# TransmissorTori.net
KiCad netlist of a schematic drawn in EAGLE
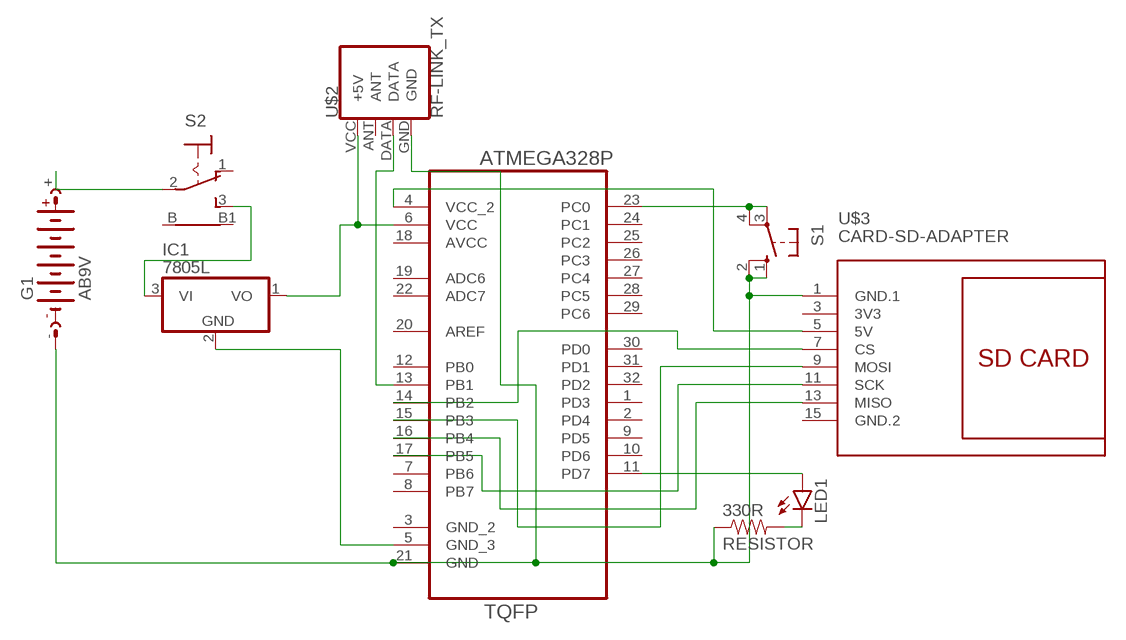
[diagram p0: schematic, sheet 1]

(export (version "E")
  (design (tool "Eeschema 10.0.6"))
  (components
    (comp (ref "330R")
      (value "RESISTOR")
      (footprint "eagle-import:0603RES")
      (libsource (lib "eagle-import") (part "RESISTOR"))
    )
    (comp (ref "G1")
      (value "AB9V")
      (footprint "eagle-import:AB9V")
      (libsource (lib "eagle-import") (part "AB9V"))
    )
    (comp (ref "IC1")
      (value "7805L")
      (footprint "eagle-import:TO92")
      (libsource (lib "eagle-import") (part "78L05"))
    )
    (comp (ref "LED1")
      (value "LED5MM")
      (footprint "eagle-import:LED5MM")
      (libsource (lib "eagle-import") (part "LED5MM"))
    )
    (comp (ref "S1")
      (value "10-XX")
      (footprint "eagle-import:B3F-10XX")
      (fields (field (name "MPN") "B3F-1000"))
      (libsource (lib "eagle-import") (part "10-XX"))
    )
    (comp (ref "S2")
      (value "9070-1W")
      (footprint "eagle-import:9070-1W")
      (libsource (lib "eagle-import") (part "9070-1W"))
    )
    (comp (ref "U$2")
      (value "RF-LINK_TX")
      (footprint "eagle-import:RF-LINK_TX")
      (libsource (lib "eagle-import") (part "RF-LINK_TX"))
    )
    (comp (ref "U$3")
      (value "CARD-SD-ADAPTER")
      (footprint "eagle-import:CARD-SD-ADAPTER")
      (libsource (lib "eagle-import") (part "CARD-SD-ADAPTER"))
    )
    (comp (ref "U1")
      (value "ATMEGA328P-AU")
      (footprint "eagle-import:QFP80P900X900X120-32N")
      (libsource (lib "eagle-import") (part "ATMEGA328P-AU"))
    )
  )
  (nets
    (net (code "1") (name "/3V3") (class "Default")
      (node (ref "U$3") (pin "3") (pinfunction "3V3_3") (pintype "power_in"))
    )
    (net (code "2") (name "/AVCC") (class "Default")
      (node (ref "U1") (pin "18") (pinfunction "AVCC_18") (pintype "power_in"))
    )
    (net (code "3") (name "/GND.2") (class "Default")
      (node (ref "U$3") (pin "15") (pinfunction "GND.2_15") (pintype "power_in"))
    )
    (net (code "4") (name "Net-(IC1-GND)") (class "Default")
      (node (ref "IC1") (pin "2") (pinfunction "GND_2") (pintype "passive"))
      (node (ref "U1") (pin "5") (pinfunction "GND_3_5") (pintype "passive"))
    )
    (net (code "5") (name "Net-(IC1-VI)") (class "Default")
      (node (ref "IC1") (pin "3") (pinfunction "VI_3") (pintype "input"))
      (node (ref "S2") (pin "3") (pinfunction "S_3") (pintype "passive"))
    )
    (net (code "6") (name "Net-(IC1-VO)") (class "Default")
      (node (ref "IC1") (pin "1") (pinfunction "VO_1") (pintype "passive"))
      (node (ref "U$2") (pin "VCC") (pinfunction "+5V_VCC") (pintype "power_in"))
      (node (ref "U1") (pin "6") (pinfunction "VCC_6") (pintype "power_in"))
    )
    (net (code "7") (name "Net-(LED1-C)") (class "Default")
      (node (ref "330R") (pin "2") (pinfunction "2_2") (pintype "passive"))
      (node (ref "LED1") (pin "K") (pinfunction "C_K") (pintype "passive"))
    )
    (net (code "8") (name "Net-(S1-P)") (class "Default")
      (node (ref "S1") (pin "3") (pinfunction "P_3") (pintype "passive"))
      (node (ref "S1") (pin "4") (pinfunction "P1_4") (pintype "passive"))
      (node (ref "U1") (pin "23") (pinfunction "PC0_23") (pintype "bidirectional"))
    )
    (net (code "9") (name "Net-(S1-S)") (class "Default")
      (node (ref "330R") (pin "1") (pinfunction "1_1") (pintype "passive"))
      (node (ref "G1") (pin "-") (pinfunction "-_-") (pintype "passive"))
      (node (ref "S1") (pin "1") (pinfunction "S_1") (pintype "passive"))
      (node (ref "S1") (pin "2") (pinfunction "S1_2") (pintype "passive"))
      (node (ref "U$2") (pin "GND") (pinfunction "GND_GND") (pintype "power_in"))
      (node (ref "U$3") (pin "1") (pinfunction "GND.1_1") (pintype "power_in"))
      (node (ref "U1") (pin "21") (pinfunction "GND_21") (pintype "passive"))
    )
    (net (code "10") (name "Net-(S2-P)") (class "Default")
      (node (ref "G1") (pin "+") (pinfunction "+_+") (pintype "passive"))
      (node (ref "S2") (pin "2") (pinfunction "P_2") (pintype "passive"))
    )
    (net (code "11") (name "Net-(U$3-5V)") (class "Default")
      (node (ref "U$3") (pin "5") (pinfunction "5V_5") (pintype "power_in"))
      (node (ref "U1") (pin "4") (pinfunction "VCC_2_4") (pintype "power_in"))
    )
    (net (code "12") (name "Net-(U$3-CS)") (class "Default")
      (node (ref "U$3") (pin "7") (pinfunction "CS_7") (pintype "bidirectional"))
      (node (ref "U1") (pin "14") (pinfunction "PB2_14") (pintype "bidirectional"))
    )
    (net (code "13") (name "Net-(U$3-MISO)") (class "Default")
      (node (ref "U$3") (pin "13") (pinfunction "MISO_13") (pintype "bidirectional"))
      (node (ref "U1") (pin "16") (pinfunction "PB4_16") (pintype "bidirectional"))
    )
    (net (code "14") (name "Net-(U$3-MOSI)") (class "Default")
      (node (ref "U$3") (pin "9") (pinfunction "MOSI_9") (pintype "bidirectional"))
      (node (ref "U1") (pin "15") (pinfunction "PB3_15") (pintype "bidirectional"))
    )
    (net (code "15") (name "Net-(U$3-SCK)") (class "Default")
      (node (ref "U$3") (pin "11") (pinfunction "SCK_11") (pintype "bidirectional"))
      (node (ref "U1") (pin "17") (pinfunction "PB5_17") (pintype "bidirectional"))
    )
    (net (code "16") (name "Net-(U1-PB1)") (class "Default")
      (node (ref "U$2") (pin "DATA") (pinfunction "DATA_DATA") (pintype "input"))
      (node (ref "U1") (pin "13") (pinfunction "PB1_13") (pintype "bidirectional"))
    )
    (net (code "17") (name "Net-(U1-PD7)") (class "Default")
      (node (ref "LED1") (pin "A") (pinfunction "A_A") (pintype "passive"))
      (node (ref "U1") (pin "11") (pinfunction "PD7_11") (pintype "bidirectional"))
    )
    (net (code "18") (name "unconnected-(S2-O-Pad1)") (class "Default")
      (node (ref "S2") (pin "1") (pinfunction "O_1") (pintype "passive"))
    )
    (net (code "19") (name "unconnected-(S2-PadB)") (class "Default")
      (node (ref "S2") (pin "B") (pinfunction "B_B") (pintype "passive"))
    )
    (net (code "20") (name "unconnected-(S2-PadB1)") (class "Default")
      (node (ref "S2") (pin "B1") (pinfunction "B1_B1") (pintype "passive"))
    )
    (net (code "21") (name "unconnected-(U$2-PadANT)") (class "Default")
      (node (ref "U$2") (pin "ANT") (pinfunction "ANT_ANT") (pintype "passive"))
    )
    (net (code "22") (name "unconnected-(U1-ADC6-Pad19)") (class "Default")
      (node (ref "U1") (pin "19") (pinfunction "ADC6_19") (pintype "input"))
    )
    (net (code "23") (name "unconnected-(U1-ADC7-Pad22)") (class "Default")
      (node (ref "U1") (pin "22") (pinfunction "ADC7_22") (pintype "input"))
    )
    (net (code "24") (name "unconnected-(U1-AREF-Pad20)") (class "Default")
      (node (ref "U1") (pin "20") (pinfunction "AREF_20") (pintype "input"))
    )
    (net (code "25") (name "unconnected-(U1-GND_2-Pad3)") (class "Default")
      (node (ref "U1") (pin "3") (pinfunction "GND_2_3") (pintype "passive"))
    )
    (net (code "26") (name "unconnected-(U1-PB0-Pad12)") (class "Default")
      (node (ref "U1") (pin "12") (pinfunction "PB0_12") (pintype "bidirectional"))
    )
    (net (code "27") (name "unconnected-(U1-PB6-Pad7)") (class "Default")
      (node (ref "U1") (pin "7") (pinfunction "PB6_7") (pintype "bidirectional"))
    )
    (net (code "28") (name "unconnected-(U1-PB7-Pad8)") (class "Default")
      (node (ref "U1") (pin "8") (pinfunction "PB7_8") (pintype "bidirectional"))
    )
    (net (code "29") (name "unconnected-(U1-PC1-Pad24)") (class "Default")
      (node (ref "U1") (pin "24") (pinfunction "PC1_24") (pintype "bidirectional"))
    )
    (net (code "30") (name "unconnected-(U1-PC2-Pad25)") (class "Default")
      (node (ref "U1") (pin "25") (pinfunction "PC2_25") (pintype "bidirectional"))
    )
    (net (code "31") (name "unconnected-(U1-PC3-Pad26)") (class "Default")
      (node (ref "U1") (pin "26") (pinfunction "PC3_26") (pintype "bidirectional"))
    )
    (net (code "32") (name "unconnected-(U1-PC4-Pad27)") (class "Default")
      (node (ref "U1") (pin "27") (pinfunction "PC4_27") (pintype "bidirectional"))
    )
    (net (code "33") (name "unconnected-(U1-PC5-Pad28)") (class "Default")
      (node (ref "U1") (pin "28") (pinfunction "PC5_28") (pintype "bidirectional"))
    )
    (net (code "34") (name "unconnected-(U1-PC6-Pad29)") (class "Default")
      (node (ref "U1") (pin "29") (pinfunction "PC6_29") (pintype "bidirectional"))
    )
    (net (code "35") (name "unconnected-(U1-PD0-Pad30)") (class "Default")
      (node (ref "U1") (pin "30") (pinfunction "PD0_30") (pintype "bidirectional"))
    )
    (net (code "36") (name "unconnected-(U1-PD1-Pad31)") (class "Default")
      (node (ref "U1") (pin "31") (pinfunction "PD1_31") (pintype "bidirectional"))
    )
    (net (code "37") (name "unconnected-(U1-PD2-Pad32)") (class "Default")
      (node (ref "U1") (pin "32") (pinfunction "PD2_32") (pintype "bidirectional"))
    )
    (net (code "38") (name "unconnected-(U1-PD3-Pad1)") (class "Default")
      (node (ref "U1") (pin "1") (pinfunction "PD3_1") (pintype "bidirectional"))
    )
    (net (code "39") (name "unconnected-(U1-PD4-Pad2)") (class "Default")
      (node (ref "U1") (pin "2") (pinfunction "PD4_2") (pintype "bidirectional"))
    )
    (net (code "40") (name "unconnected-(U1-PD5-Pad9)") (class "Default")
      (node (ref "U1") (pin "9") (pinfunction "PD5_9") (pintype "bidirectional"))
    )
    (net (code "41") (name "unconnected-(U1-PD6-Pad10)") (class "Default")
      (node (ref "U1") (pin "10") (pinfunction "PD6_10") (pintype "bidirectional"))
    )
  )
)
